# whistler.net
KiCad netlist of a schematic drawn in EAGLE
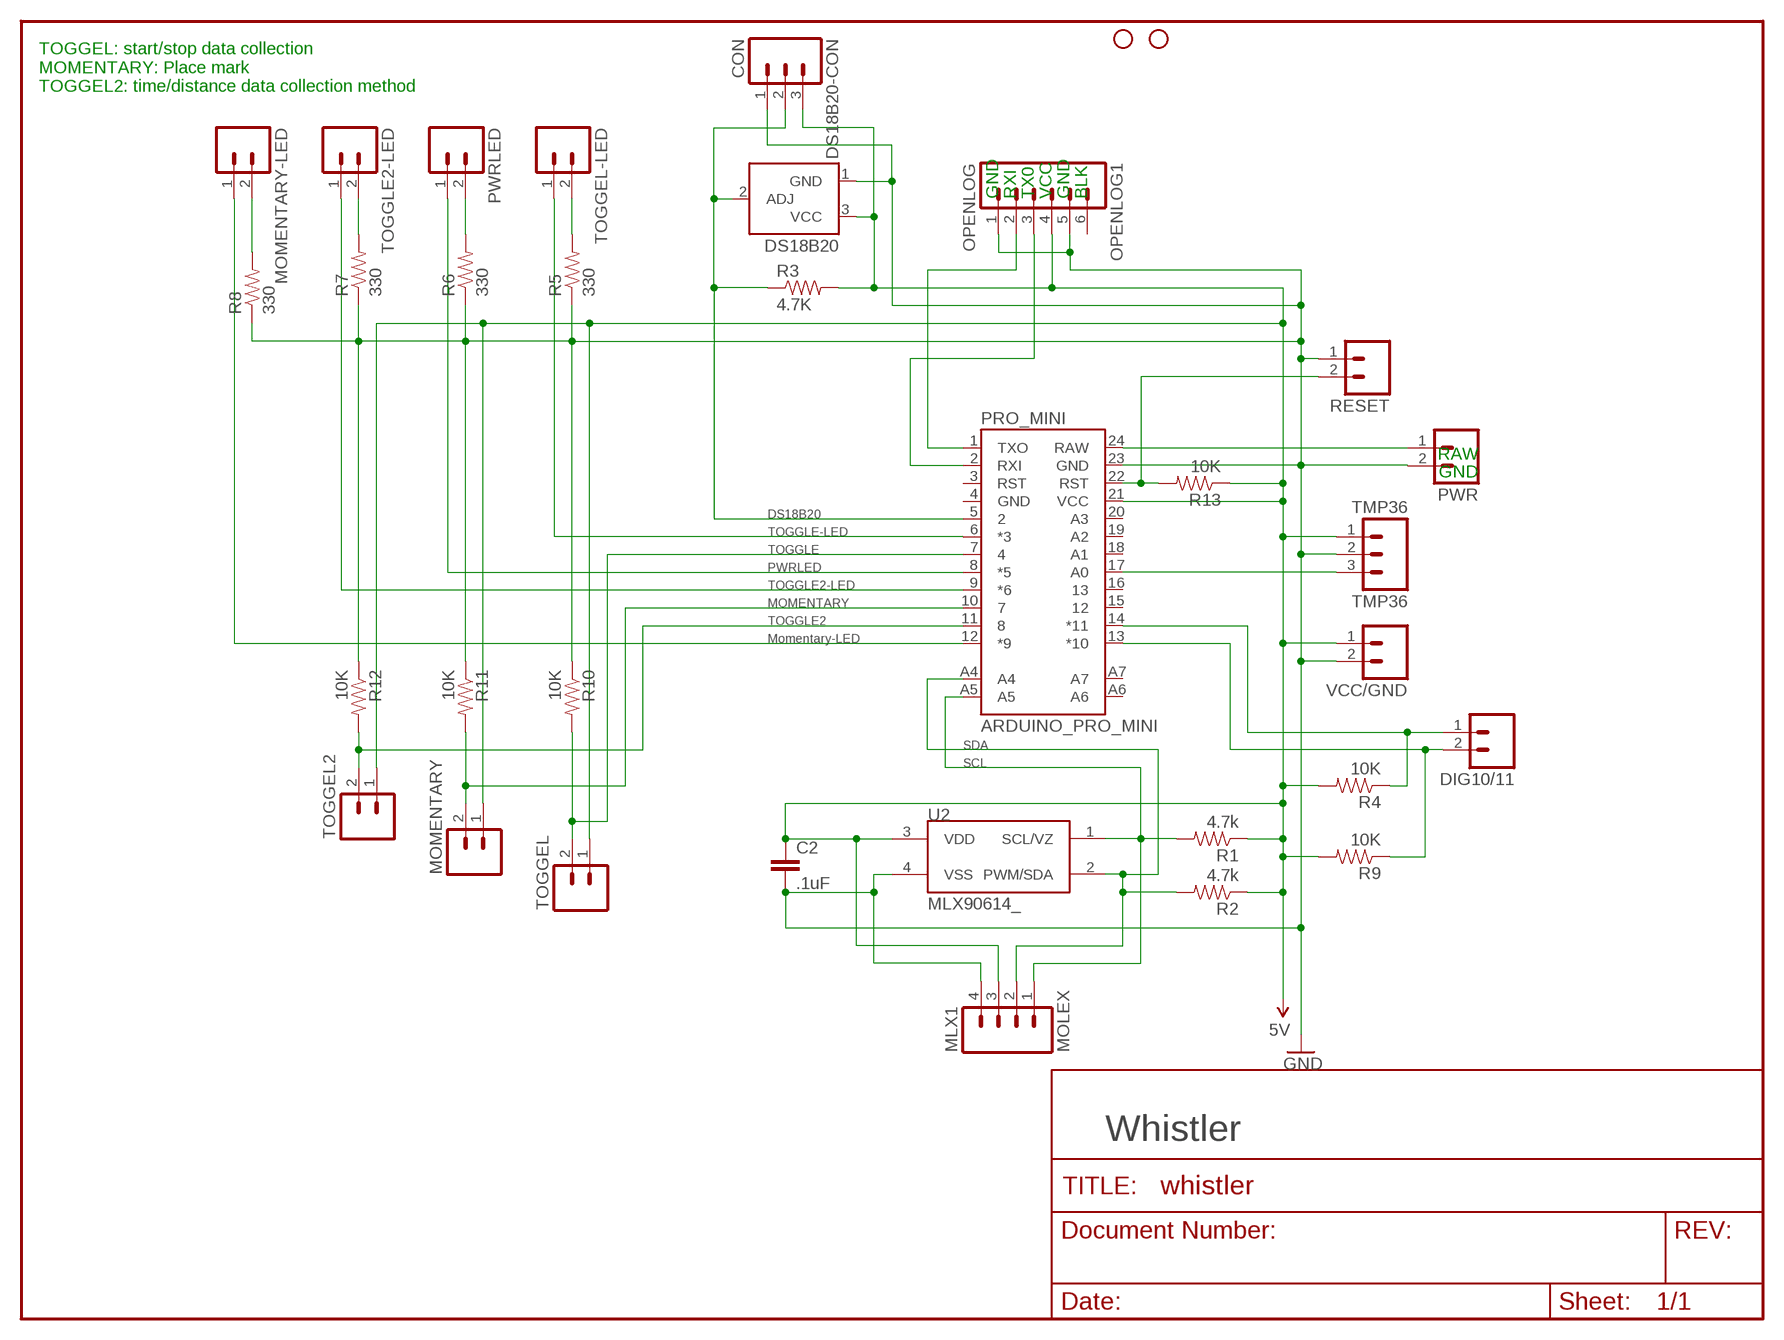
[diagram p0: schematic, sheet 1]

(export (version "E")
  (design (tool "Eeschema 10.0.6"))
  (components
    (comp (ref "C2")
      (value ".1uF")
      (footprint "eagle-import:CAP-PTH-SMALL-KIT")
      (libsource (lib "eagle-import") (part "0.1UF-50V-20%(PTH)KIT-EZ"))
    )
    (comp (ref "DIG10/11")
      (value "M023.5MM_LOCK")
      (footprint "eagle-import:SCREWTERMINAL-3.5MM-2_LOCK")
      (libsource (lib "eagle-import") (part "M023.5MM_LOCK"))
    )
    (comp (ref "DS18B20")
      (value "TEMPERATURE-SENSOR")
      (footprint "eagle-import:TO-92")
      (libsource (lib "eagle-import") (part "TEMPERATURE-SENSOR"))
    )
    (comp (ref "DS18B20-CON")
      (value "CON")
      (footprint "eagle-import:SCREWTERMINAL-3.5MM-3_LOCK.007S")
      (libsource (lib "eagle-import") (part "M03SCREW_LOCK"))
    )
    (comp (ref "JP6")
      (value "STAND-OFFTIGHT")
      (footprint "eagle-import:STAND-OFF-TIGHT")
      (libsource (lib "eagle-import") (part "STAND-OFFTIGHT"))
    )
    (comp (ref "JP7")
      (value "STAND-OFFTIGHT")
      (footprint "eagle-import:STAND-OFF-TIGHT")
      (libsource (lib "eagle-import") (part "STAND-OFFTIGHT"))
    )
    (comp (ref "MLX1")
      (value "MOLEX")
      (footprint "eagle-import:1X04-1MM-RA")
      (libsource (lib "eagle-import") (part "M04SMD2"))
    )
    (comp (ref "MOMENTARY")
      (value "M023.5MM_LOCK")
      (footprint "eagle-import:SCREWTERMINAL-3.5MM-2_LOCK")
      (libsource (lib "eagle-import") (part "M023.5MM_LOCK"))
    )
    (comp (ref "MOMENTARY-LED")
      (value "M023.5MM_LOCK")
      (footprint "eagle-import:SCREWTERMINAL-3.5MM-2_LOCK")
      (libsource (lib "eagle-import") (part "M023.5MM_LOCK"))
    )
    (comp (ref "OPENLOG1")
      (value "OPENLOG")
      (footprint "eagle-import:1X06_LOCK")
      (libsource (lib "eagle-import") (part "M06LOCK"))
    )
    (comp (ref "PRO_MINI")
      (value "ARDUINO_PRO_MINI")
      (footprint "eagle-import:ARDUINO_PRO_MINI")
      (libsource (lib "eagle-import") (part "ARDUINO_PRO_MINI"))
    )
    (comp (ref "PWR")
      (value "M023.5MM_LOCK")
      (footprint "eagle-import:SCREWTERMINAL-3.5MM-2_LOCK")
      (libsource (lib "eagle-import") (part "M023.5MM_LOCK"))
    )
    (comp (ref "PWRLED")
      (value "M023.5MM_LOCK")
      (footprint "eagle-import:SCREWTERMINAL-3.5MM-2_LOCK")
      (libsource (lib "eagle-import") (part "M023.5MM_LOCK"))
    )
    (comp (ref "R1")
      (value "4.7k")
      (footprint "eagle-import:AXIAL-0.4")
      (libsource (lib "eagle-import") (part "RESISTORPTH-1/4W"))
    )
    (comp (ref "R2")
      (value "4.7k")
      (footprint "eagle-import:AXIAL-0.4")
      (libsource (lib "eagle-import") (part "RESISTORPTH-1/4W"))
    )
    (comp (ref "R3")
      (value "4.7K")
      (footprint "eagle-import:AXIAL-0.4")
      (libsource (lib "eagle-import") (part "RESISTORPTH-1/4W"))
    )
    (comp (ref "R4")
      (value "10K")
      (footprint "eagle-import:0603-RES")
      (libsource (lib "eagle-import") (part "10KOHM1/10W1%(0603)0603"))
    )
    (comp (ref "R5")
      (value "330")
      (footprint "eagle-import:0603-RES")
      (libsource (lib "eagle-import") (part "330OHM1/10W1%(0603)"))
    )
    (comp (ref "R6")
      (value "330")
      (footprint "eagle-import:0603-RES")
      (libsource (lib "eagle-import") (part "330OHM1/10W1%(0603)"))
    )
    (comp (ref "R7")
      (value "330")
      (footprint "eagle-import:0603-RES")
      (libsource (lib "eagle-import") (part "330OHM1/10W1%(0603)"))
    )
    (comp (ref "R8")
      (value "330")
      (footprint "eagle-import:0603-RES")
      (libsource (lib "eagle-import") (part "330OHM1/10W1%(0603)"))
    )
    (comp (ref "R9")
      (value "10K")
      (footprint "eagle-import:0603-RES")
      (libsource (lib "eagle-import") (part "10KOHM1/10W1%(0603)0603"))
    )
    (comp (ref "R10")
      (value "10K")
      (footprint "eagle-import:0603-RES")
      (libsource (lib "eagle-import") (part "10KOHM1/10W1%(0603)0603"))
    )
    (comp (ref "R11")
      (value "10K")
      (footprint "eagle-import:0603-RES")
      (libsource (lib "eagle-import") (part "10KOHM1/10W1%(0603)0603"))
    )
    (comp (ref "R12")
      (value "10K")
      (footprint "eagle-import:0603-RES")
      (libsource (lib "eagle-import") (part "10KOHM1/10W1%(0603)0603"))
    )
    (comp (ref "R13")
      (value "10K")
      (footprint "eagle-import:0603-RES")
      (libsource (lib "eagle-import") (part "10KOHM1/10W1%(0603)0603"))
    )
    (comp (ref "RESET")
      (value "M023.5MM_LOCK")
      (footprint "eagle-import:SCREWTERMINAL-3.5MM-2_LOCK")
      (libsource (lib "eagle-import") (part "M023.5MM_LOCK"))
    )
    (comp (ref "TMP36")
      (value "TMP36")
      (footprint "eagle-import:SCREWTERMINAL-3.5MM-3_LOCK.007S")
      (libsource (lib "eagle-import") (part "M03SCREW_LOCK"))
    )
    (comp (ref "TOGGEL")
      (value "M023.5MM_LOCK")
      (footprint "eagle-import:SCREWTERMINAL-3.5MM-2_LOCK")
      (libsource (lib "eagle-import") (part "M023.5MM_LOCK"))
    )
    (comp (ref "TOGGEL-LED")
      (value "M023.5MM_LOCK")
      (footprint "eagle-import:SCREWTERMINAL-3.5MM-2_LOCK")
      (libsource (lib "eagle-import") (part "M023.5MM_LOCK"))
    )
    (comp (ref "TOGGEL2")
      (value "M023.5MM_LOCK")
      (footprint "eagle-import:SCREWTERMINAL-3.5MM-2_LOCK")
      (libsource (lib "eagle-import") (part "M023.5MM_LOCK"))
    )
    (comp (ref "TOGGLE2-LED")
      (value "M023.5MM_LOCK")
      (footprint "eagle-import:SCREWTERMINAL-3.5MM-2_LOCK")
      (libsource (lib "eagle-import") (part "M023.5MM_LOCK"))
    )
    (comp (ref "U2")
      (value "MLX90614_")
      (footprint "eagle-import:TO-39")
      (libsource (lib "eagle-import") (part "MLX90614_"))
    )
    (comp (ref "VCC/GND")
      (value "M023.5MM_LOCK")
      (footprint "eagle-import:SCREWTERMINAL-3.5MM-2_LOCK")
      (libsource (lib "eagle-import") (part "M023.5MM_LOCK"))
    )
  )
  (nets
    (net (code "1") (name "5V") (class "Default")
      (node (ref "C2") (pin "1") (pinfunction "1_1") (pintype "passive"))
      (node (ref "DS18B20") (pin "3") (pinfunction "VCC_3") (pintype "bidirectional"))
      (node (ref "DS18B20-CON") (pin "3") (pinfunction "3_3") (pintype "passive"))
      (node (ref "MLX1") (pin "3") (pinfunction "3_3") (pintype "passive"))
      (node (ref "MOMENTARY") (pin "1") (pinfunction "1_1") (pintype "passive"))
      (node (ref "OPENLOG1") (pin "4") (pinfunction "4_4") (pintype "passive"))
      (node (ref "PRO_MINI") (pin "21") (pinfunction "VCC_21") (pintype "bidirectional"))
      (node (ref "R1") (pin "P$1") (pinfunction "1_P$1") (pintype "passive"))
      (node (ref "R13") (pin "1") (pinfunction "1_1") (pintype "passive"))
      (node (ref "R2") (pin "P$1") (pinfunction "1_P$1") (pintype "passive"))
      (node (ref "R3") (pin "P$2") (pinfunction "2_P$2") (pintype "passive"))
      (node (ref "R4") (pin "2") (pinfunction "2_2") (pintype "passive"))
      (node (ref "R9") (pin "2") (pinfunction "2_2") (pintype "passive"))
      (node (ref "TMP36") (pin "1") (pinfunction "1_1") (pintype "passive"))
      (node (ref "TOGGEL") (pin "1") (pinfunction "1_1") (pintype "passive"))
      (node (ref "TOGGEL2") (pin "1") (pinfunction "1_1") (pintype "passive"))
      (node (ref "U2") (pin "3") (pinfunction "VDD_3") (pintype "bidirectional"))
      (node (ref "VCC/GND") (pin "1") (pinfunction "1_1") (pintype "passive"))
    )
    (net (code "2") (name "GND") (class "Default")
      (node (ref "C2") (pin "2") (pinfunction "2_2") (pintype "passive"))
      (node (ref "DS18B20") (pin "1") (pinfunction "GND_1") (pintype "bidirectional"))
      (node (ref "DS18B20-CON") (pin "1") (pinfunction "1_1") (pintype "passive"))
      (node (ref "MLX1") (pin "4") (pinfunction "4_4") (pintype "passive"))
      (node (ref "OPENLOG1") (pin "1") (pinfunction "1_1") (pintype "passive"))
      (node (ref "OPENLOG1") (pin "5") (pinfunction "5_5") (pintype "passive"))
      (node (ref "PRO_MINI") (pin "23") (pinfunction "GND_23") (pintype "bidirectional"))
      (node (ref "PWR") (pin "2") (pinfunction "2_2") (pintype "passive"))
      (node (ref "R10") (pin "1") (pinfunction "1_1") (pintype "passive"))
      (node (ref "R11") (pin "1") (pinfunction "1_1") (pintype "passive"))
      (node (ref "R12") (pin "1") (pinfunction "1_1") (pintype "passive"))
      (node (ref "R5") (pin "1") (pinfunction "1_1") (pintype "passive"))
      (node (ref "R6") (pin "1") (pinfunction "1_1") (pintype "passive"))
      (node (ref "R7") (pin "1") (pinfunction "1_1") (pintype "passive"))
      (node (ref "R8") (pin "1") (pinfunction "1_1") (pintype "passive"))
      (node (ref "RESET") (pin "1") (pinfunction "1_1") (pintype "passive"))
      (node (ref "TMP36") (pin "2") (pinfunction "2_2") (pintype "passive"))
      (node (ref "U2") (pin "4") (pinfunction "VSS_4") (pintype "bidirectional"))
      (node (ref "VCC/GND") (pin "2") (pinfunction "2_2") (pintype "passive"))
    )
    (net (code "3") (name "Net-(DS18B20-ADJ)") (class "Default")
      (node (ref "DS18B20") (pin "2") (pinfunction "ADJ_2") (pintype "bidirectional"))
      (node (ref "DS18B20-CON") (pin "2") (pinfunction "2_2") (pintype "passive"))
      (node (ref "PRO_MINI") (pin "5") (pinfunction "2_5") (pintype "bidirectional"))
      (node (ref "R3") (pin "P$1") (pinfunction "1_P$1") (pintype "passive"))
    )
    (net (code "4") (name "Net-(MOMENTARY-LED-Pad2)") (class "Default")
      (node (ref "MOMENTARY-LED") (pin "2") (pinfunction "2_2") (pintype "passive"))
      (node (ref "R8") (pin "2") (pinfunction "2_2") (pintype "passive"))
    )
    (net (code "5") (name "Net-(PRO_MINI-*3)") (class "Default")
      (node (ref "PRO_MINI") (pin "6") (pinfunction "*3_6") (pintype "bidirectional"))
      (node (ref "TOGGEL-LED") (pin "1") (pinfunction "1_1") (pintype "passive"))
    )
    (net (code "6") (name "Net-(PRO_MINI-*5)") (class "Default")
      (node (ref "PRO_MINI") (pin "8") (pinfunction "*5_8") (pintype "bidirectional"))
      (node (ref "PWRLED") (pin "1") (pinfunction "1_1") (pintype "passive"))
    )
    (net (code "7") (name "Net-(PRO_MINI-*6)") (class "Default")
      (node (ref "PRO_MINI") (pin "9") (pinfunction "*6_9") (pintype "bidirectional"))
      (node (ref "TOGGLE2-LED") (pin "1") (pinfunction "1_1") (pintype "passive"))
    )
    (net (code "8") (name "Net-(PRO_MINI-*9)") (class "Default")
      (node (ref "MOMENTARY-LED") (pin "1") (pinfunction "1_1") (pintype "passive"))
      (node (ref "PRO_MINI") (pin "12") (pinfunction "*9_12") (pintype "bidirectional"))
    )
    (net (code "9") (name "Net-(PRO_MINI-*10)") (class "Default")
      (node (ref "DIG10/11") (pin "2") (pinfunction "2_2") (pintype "passive"))
      (node (ref "PRO_MINI") (pin "13") (pinfunction "*10_13") (pintype "bidirectional"))
      (node (ref "R9") (pin "1") (pinfunction "1_1") (pintype "passive"))
    )
    (net (code "10") (name "Net-(PRO_MINI-*11)") (class "Default")
      (node (ref "DIG10/11") (pin "1") (pinfunction "1_1") (pintype "passive"))
      (node (ref "PRO_MINI") (pin "14") (pinfunction "*11_14") (pintype "bidirectional"))
      (node (ref "R4") (pin "1") (pinfunction "1_1") (pintype "passive"))
    )
    (net (code "11") (name "Net-(PRO_MINI-4)") (class "Default")
      (node (ref "PRO_MINI") (pin "7") (pinfunction "4_7") (pintype "bidirectional"))
      (node (ref "R10") (pin "2") (pinfunction "2_2") (pintype "passive"))
      (node (ref "TOGGEL") (pin "2") (pinfunction "2_2") (pintype "passive"))
    )
    (net (code "12") (name "Net-(PRO_MINI-7)") (class "Default")
      (node (ref "MOMENTARY") (pin "2") (pinfunction "2_2") (pintype "passive"))
      (node (ref "PRO_MINI") (pin "10") (pinfunction "7_10") (pintype "bidirectional"))
      (node (ref "R11") (pin "2") (pinfunction "2_2") (pintype "passive"))
    )
    (net (code "13") (name "Net-(PRO_MINI-8)") (class "Default")
      (node (ref "PRO_MINI") (pin "11") (pinfunction "8_11") (pintype "bidirectional"))
      (node (ref "R12") (pin "2") (pinfunction "2_2") (pintype "passive"))
      (node (ref "TOGGEL2") (pin "2") (pinfunction "2_2") (pintype "passive"))
    )
    (net (code "14") (name "Net-(PRO_MINI-A0)") (class "Default")
      (node (ref "PRO_MINI") (pin "17") (pinfunction "A0_17") (pintype "bidirectional"))
      (node (ref "TMP36") (pin "3") (pinfunction "3_3") (pintype "passive"))
    )
    (net (code "15") (name "Net-(PRO_MINI-RAW)") (class "Default")
      (node (ref "PRO_MINI") (pin "24") (pinfunction "RAW_24") (pintype "bidirectional"))
      (node (ref "PWR") (pin "1") (pinfunction "1_1") (pintype "passive"))
    )
    (net (code "16") (name "Net-(PRO_MINI-RST-Pad22)") (class "Default")
      (node (ref "PRO_MINI") (pin "22") (pinfunction "RST_22") (pintype "bidirectional"))
      (node (ref "R13") (pin "2") (pinfunction "2_2") (pintype "passive"))
      (node (ref "RESET") (pin "2") (pinfunction "2_2") (pintype "passive"))
    )
    (net (code "17") (name "Net-(PRO_MINI-RXI)") (class "Default")
      (node (ref "OPENLOG1") (pin "3") (pinfunction "3_3") (pintype "passive"))
      (node (ref "PRO_MINI") (pin "2") (pinfunction "RXI_2") (pintype "bidirectional"))
    )
    (net (code "18") (name "Net-(PRO_MINI-TXO)") (class "Default")
      (node (ref "OPENLOG1") (pin "2") (pinfunction "2_2") (pintype "passive"))
      (node (ref "PRO_MINI") (pin "1") (pinfunction "TXO_1") (pintype "bidirectional"))
    )
    (net (code "19") (name "Net-(PWRLED-Pad2)") (class "Default")
      (node (ref "PWRLED") (pin "2") (pinfunction "2_2") (pintype "passive"))
      (node (ref "R6") (pin "2") (pinfunction "2_2") (pintype "passive"))
    )
    (net (code "20") (name "Net-(R1-2)") (class "Default")
      (node (ref "MLX1") (pin "1") (pinfunction "1_1") (pintype "passive"))
      (node (ref "PRO_MINI") (pin "A5") (pinfunction "A5_A5") (pintype "bidirectional"))
      (node (ref "R1") (pin "P$2") (pinfunction "2_P$2") (pintype "passive"))
      (node (ref "U2") (pin "1") (pinfunction "SCL/VZ_1") (pintype "bidirectional"))
    )
    (net (code "21") (name "Net-(R2-2)") (class "Default")
      (node (ref "MLX1") (pin "2") (pinfunction "2_2") (pintype "passive"))
      (node (ref "PRO_MINI") (pin "A4") (pinfunction "A4_A4") (pintype "bidirectional"))
      (node (ref "R2") (pin "P$2") (pinfunction "2_P$2") (pintype "passive"))
      (node (ref "U2") (pin "2") (pinfunction "PWM/SDA_2") (pintype "bidirectional"))
    )
    (net (code "22") (name "Net-(R5-Pad2)") (class "Default")
      (node (ref "R5") (pin "2") (pinfunction "2_2") (pintype "passive"))
      (node (ref "TOGGEL-LED") (pin "2") (pinfunction "2_2") (pintype "passive"))
    )
    (net (code "23") (name "Net-(R7-Pad2)") (class "Default")
      (node (ref "R7") (pin "2") (pinfunction "2_2") (pintype "passive"))
      (node (ref "TOGGLE2-LED") (pin "2") (pinfunction "2_2") (pintype "passive"))
    )
    (net (code "24") (name "unconnected-(OPENLOG1-Pad6)") (class "Default")
      (node (ref "OPENLOG1") (pin "6") (pinfunction "6_6") (pintype "passive"))
    )
    (net (code "25") (name "unconnected-(PRO_MINI-12-Pad15)") (class "Default")
      (node (ref "PRO_MINI") (pin "15") (pinfunction "12_15") (pintype "bidirectional"))
    )
    (net (code "26") (name "unconnected-(PRO_MINI-13-Pad16)") (class "Default")
      (node (ref "PRO_MINI") (pin "16") (pinfunction "13_16") (pintype "bidirectional"))
    )
    (net (code "27") (name "unconnected-(PRO_MINI-A1-Pad18)") (class "Default")
      (node (ref "PRO_MINI") (pin "18") (pinfunction "A1_18") (pintype "bidirectional"))
    )
    (net (code "28") (name "unconnected-(PRO_MINI-A2-Pad19)") (class "Default")
      (node (ref "PRO_MINI") (pin "19") (pinfunction "A2_19") (pintype "bidirectional"))
    )
    (net (code "29") (name "unconnected-(PRO_MINI-A3-Pad20)") (class "Default")
      (node (ref "PRO_MINI") (pin "20") (pinfunction "A3_20") (pintype "bidirectional"))
    )
    (net (code "30") (name "unconnected-(PRO_MINI-GND-Pad4)") (class "Default")
      (node (ref "PRO_MINI") (pin "4") (pinfunction "GND_4") (pintype "bidirectional"))
    )
    (net (code "31") (name "unconnected-(PRO_MINI-PadA6)") (class "Default")
      (node (ref "PRO_MINI") (pin "A6") (pinfunction "A6_A6") (pintype "bidirectional"))
    )
    (net (code "32") (name "unconnected-(PRO_MINI-PadA7)") (class "Default")
      (node (ref "PRO_MINI") (pin "A7") (pinfunction "A7_A7") (pintype "bidirectional"))
    )
    (net (code "33") (name "unconnected-(PRO_MINI-RST-Pad3)") (class "Default")
      (node (ref "PRO_MINI") (pin "3") (pinfunction "RST_3") (pintype "bidirectional"))
    )
  )
)
